# SMC.net
KiCad netlist of a schematic drawn in Altium Designer
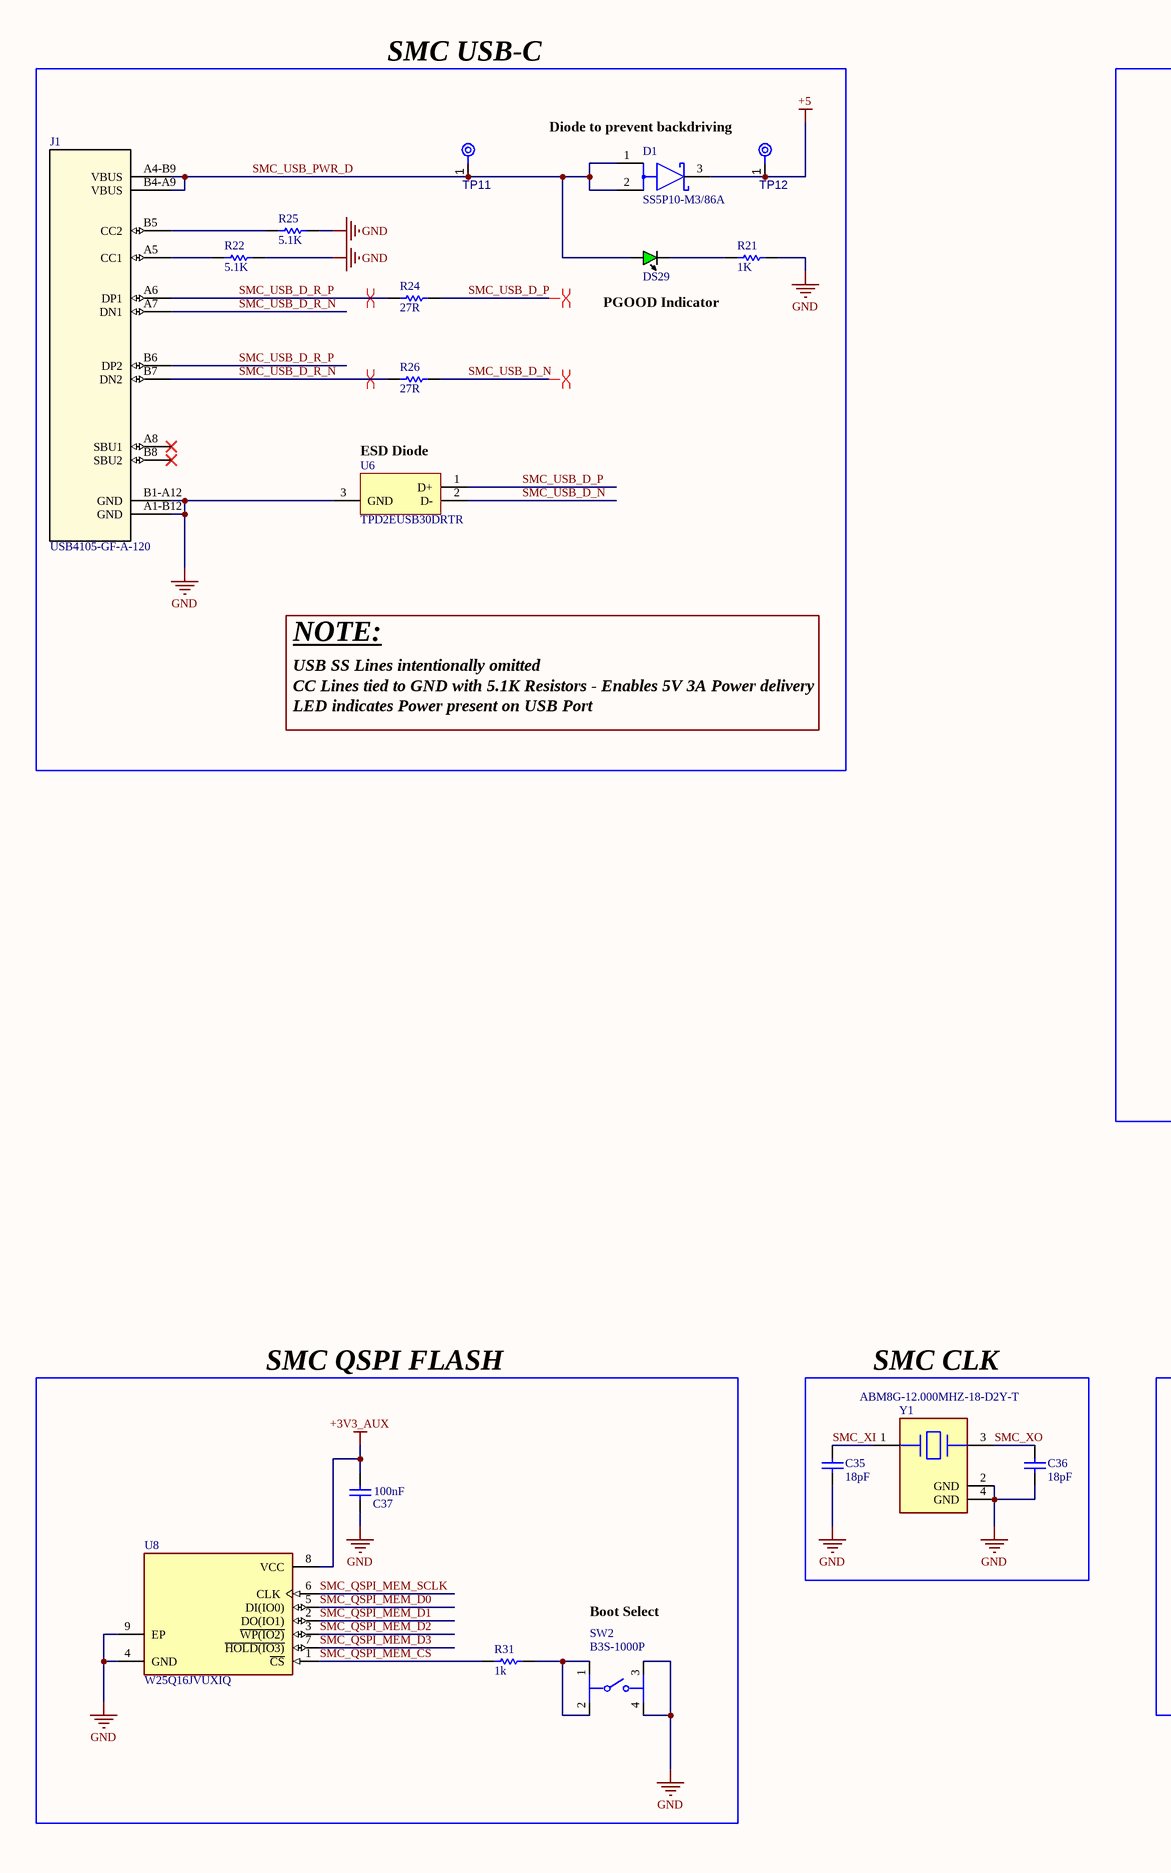
[diagram p0: SMC.SchDoc, left]
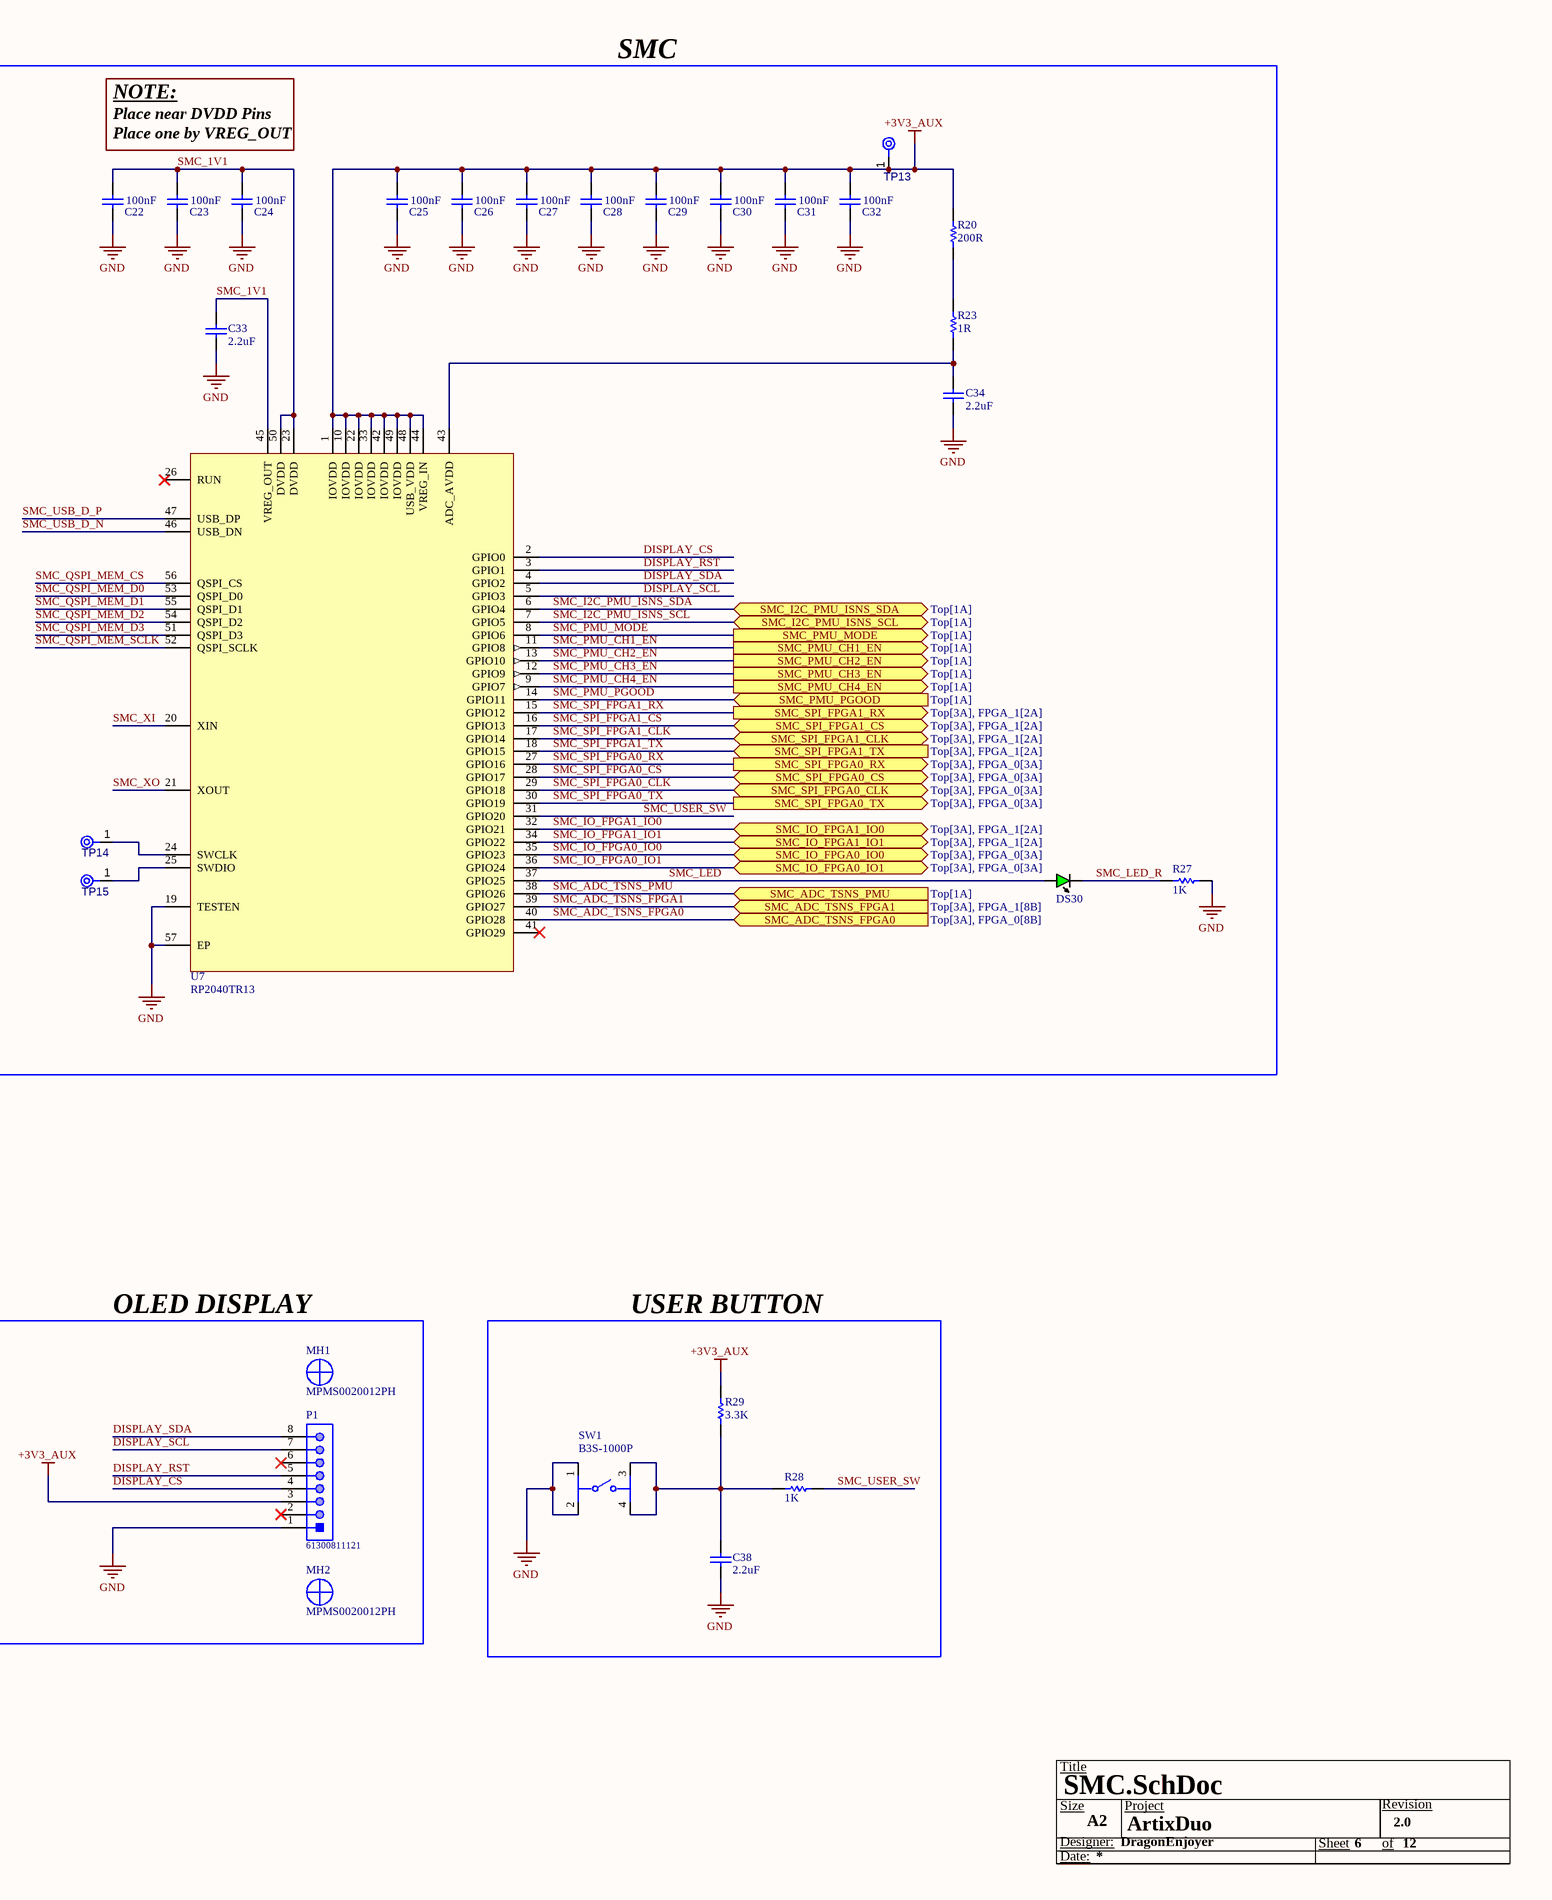
[diagram p1: SMC.SchDoc, right]

(export (version "E")
  (design (tool "Eeschema 10.0.6"))
  (components
    (comp (ref "C22")
      (value "100nF")
      (footprint "CAPC1005X05N")
      (description "Cap Ceramic 0.1uF 50V X7R 20% SMD 0402 125°C Paper T/R GRM155R71H104ME14J")
      (fields (field (name "VOLTAGE") "50V"))
      (libsource (lib "Main Workspace") (part "CAP"))
    )
    (comp (ref "C23")
      (value "100nF")
      (footprint "CAPC1005X05N")
      (description "Cap Ceramic 0.1uF 50V X7R 20% SMD 0402 125°C Paper T/R GRM155R71H104ME14J")
      (fields (field (name "VOLTAGE") "50V"))
      (libsource (lib "Main Workspace") (part "CAP"))
    )
    (comp (ref "C24")
      (value "100nF")
      (footprint "CAPC1005X05N")
      (description "Cap Ceramic 0.1uF 50V X7R 20% SMD 0402 125°C Paper T/R GRM155R71H104ME14J")
      (fields (field (name "VOLTAGE") "50V"))
      (libsource (lib "Main Workspace") (part "CAP"))
    )
    (comp (ref "C25")
      (value "100nF")
      (footprint "CAPC1005X05N")
      (description "Cap Ceramic 0.1uF 50V X7R 20% SMD 0402 125°C Paper T/R GRM155R71H104ME14J")
      (fields (field (name "VOLTAGE") "50V"))
      (libsource (lib "Main Workspace") (part "CAP"))
    )
    (comp (ref "C26")
      (value "100nF")
      (footprint "CAPC1005X05N")
      (description "Cap Ceramic 0.1uF 50V X7R 20% SMD 0402 125°C Paper T/R GRM155R71H104ME14J")
      (fields (field (name "VOLTAGE") "50V"))
      (libsource (lib "Main Workspace") (part "CAP"))
    )
    (comp (ref "C27")
      (value "100nF")
      (footprint "CAPC1005X05N")
      (description "Cap Ceramic 0.1uF 50V X7R 20% SMD 0402 125°C Paper T/R GRM155R71H104ME14J")
      (fields (field (name "VOLTAGE") "50V"))
      (libsource (lib "Main Workspace") (part "CAP"))
    )
    (comp (ref "C28")
      (value "100nF")
      (footprint "CAPC1005X05N")
      (description "Cap Ceramic 0.1uF 50V X7R 20% SMD 0402 125°C Paper T/R GRM155R71H104ME14J")
      (fields (field (name "VOLTAGE") "50V"))
      (libsource (lib "Main Workspace") (part "CAP"))
    )
    (comp (ref "C29")
      (value "100nF")
      (footprint "CAPC1005X05N")
      (description "Cap Ceramic 0.1uF 50V X7R 20% SMD 0402 125°C Paper T/R GRM155R71H104ME14J")
      (fields (field (name "VOLTAGE") "50V"))
      (libsource (lib "Main Workspace") (part "CAP"))
    )
    (comp (ref "C30")
      (value "100nF")
      (footprint "CAPC1005X05N")
      (description "Cap Ceramic 0.1uF 50V X7R 20% SMD 0402 125°C Paper T/R GRM155R71H104ME14J")
      (fields (field (name "VOLTAGE") "50V"))
      (libsource (lib "Main Workspace") (part "CAP"))
    )
    (comp (ref "C31")
      (value "100nF")
      (footprint "CAPC1005X05N")
      (description "Cap Ceramic 0.1uF 50V X7R 20% SMD 0402 125°C Paper T/R GRM155R71H104ME14J")
      (fields (field (name "VOLTAGE") "50V"))
      (libsource (lib "Main Workspace") (part "CAP"))
    )
    (comp (ref "C32")
      (value "100nF")
      (footprint "CAPC1005X05N")
      (description "Cap Ceramic 0.1uF 50V X7R 20% SMD 0402 125°C Paper T/R GRM155R71H104ME14J")
      (fields (field (name "VOLTAGE") "50V"))
      (libsource (lib "Main Workspace") (part "CAP"))
    )
    (comp (ref "C33")
      (value "2.2uF")
      (footprint "CAPC1005X55X25NL05T10")
      (description "GRM155R60J225ME15D")
      (fields (field (name "MANUFACTURER") "Murata"))
      (libsource (lib "Altium Content Vault") (part "CAP"))
    )
    (comp (ref "C34")
      (value "2.2uF")
      (footprint "CAPC1005X55X25NL05T10")
      (description "GRM155R60J225ME15D")
      (fields (field (name "MANUFACTURER") "Murata"))
      (libsource (lib "Altium Content Vault") (part "CAP"))
    )
    (comp (ref "C35")
      (value "18pF")
      (footprint "CAPC1005X55X25LL05T10")
      (fields (field (name "MANUFACTURER") "Murata") (field (name "TOLERANCE") "±5%"))
      (libsource (lib "Altium Content Vault") (part "CAP-NP-2"))
    )
    (comp (ref "C36")
      (value "18pF")
      (footprint "CAPC1005X55X25LL05T10")
      (fields (field (name "MANUFACTURER") "Murata") (field (name "TOLERANCE") "±5%"))
      (libsource (lib "Altium Content Vault") (part "CAP-NP-2"))
    )
    (comp (ref "C37")
      (value "100nF")
      (footprint "CAPC1005X05N")
      (description "Cap Ceramic 0.1uF 50V X7R 20% SMD 0402 125°C Paper T/R GRM155R71H104ME14J")
      (fields (field (name "VOLTAGE") "50V"))
      (libsource (lib "Main Workspace") (part "CAP"))
    )
    (comp (ref "C38")
      (value "2.2uF")
      (footprint "CAPC1005X55X25NL05T10")
      (description "GRM155R60J225ME15D")
      (fields (field (name "MANUFACTURER") "Murata"))
      (libsource (lib "Altium Content Vault") (part "CAP"))
    )
    (comp (ref "D1")
      (value "SS5P10-M3/86A")
      (footprint "FP-95570-MFG")
      (description "DIODE SCHOTTKY 100V 5A TO277A")
      (libsource (lib "Altium Content Vault") (part "03725f8997c85b601c823eea96032f8"))
    )
    (comp (ref "DS29")
      (value "SMLLX0603GWTR")
      (footprint "LUMX-SML-LX0603_V")
      (description "LED GREEN DIFFUSED SMD")
      (libsource (lib "Main Workspace") (part "LED-GREEN-AK-2"))
    )
    (comp (ref "DS30")
      (value "SMLLX0603GWTR")
      (footprint "LUMX-SML-LX0603_V")
      (description "LED GREEN DIFFUSED SMD")
      (libsource (lib "Main Workspace") (part "LED-GREEN-AK-2"))
    )
    (comp (ref "J1")
      (value "USB4105-GF-A-120")
      (footprint "USB4105-GF-A-120-Footprint-1")
      (libsource (lib "Main Workspace") (part "USB4105-GF-A-120"))
    )
    (comp (ref "MH1")
      (value "MPMS0020012PH")
      (footprint "BF-MPMS0020012PH")
      (description "Copper Pillar, M2 Screw")
      (fields (field (name "MANUFACTURER") "B&F Fastener Supply"))
      (libsource (lib "Main Workspace") (part "BF-MPMS0020012PH"))
    )
    (comp (ref "MH2")
      (value "MPMS0020012PH")
      (footprint "BF-MPMS0020012PH")
      (description "Copper Pillar, M2 Screw")
      (fields (field (name "MANUFACTURER") "B&F Fastener Supply"))
      (libsource (lib "Main Workspace") (part "BF-MPMS0020012PH"))
    )
    (comp (ref "P1")
      (value "61300811121")
      (footprint "61300811121")
      (description "THT Vertical Pin Header WR-PHD, Pitch 2.54 mm, Single Row, 8 pins")
      (fields (field (name "MANUFACTURER") "Wurth Elektronik") (field (name "PUBLISHER") "WurthElektronik"))
      (libsource (lib "Altium Content Vault") (part "WE-CN-1P-M-R8"))
    )
    (comp (ref "R20")
      (value "200R")
      (footprint "RESC1005X40X25NL05T05")
      (description "CRCW0402200RJNED")
      (fields (field (name "MANUFACTURER") "Vishay Dale"))
      (libsource (lib "Altium Content Vault") (part "RES"))
    )
    (comp (ref "R21")
      (value "1K")
      (footprint "RESC1005X40X25NL05T10")
      (description "CRCW04021K00FKEDHP")
      (fields (field (name "MANUFACTURER") "Vishay Dale"))
      (libsource (lib "Altium Content Vault") (part "RES"))
    )
    (comp (ref "R22")
      (value "5.1K")
      (footprint "RESC1005X40X25NL05T10")
      (description "RC0402FR-075K1L")
      (fields (field (name "MANUFACTURER") "Yageo / Phycomp"))
      (libsource (lib "Altium Content Vault") (part "RES"))
    )
    (comp (ref "R23")
      (value "1R")
      (footprint "RESC1005X40X25NL05T05")
      (description "CRCW04021R00FKED")
      (fields (field (name "MANUFACTURER") "Vishay Dale"))
      (libsource (lib "Altium Content Vault") (part "RES"))
    )
    (comp (ref "R24")
      (value "27R")
      (footprint "RESC1005X40X25NL05T10")
      (description "RC0402JR-0727RL")
      (fields (field (name "MANUFACTURER") "Yageo / Phycomp"))
      (libsource (lib "Altium Content Vault") (part "RES"))
    )
    (comp (ref "R25")
      (value "5.1K")
      (footprint "RESC1005X40X25NL05T10")
      (description "RC0402FR-075K1L")
      (fields (field (name "MANUFACTURER") "Yageo / Phycomp"))
      (libsource (lib "Altium Content Vault") (part "RES"))
    )
    (comp (ref "R26")
      (value "27R")
      (footprint "RESC1005X40X25NL05T10")
      (description "RC0402JR-0727RL")
      (fields (field (name "MANUFACTURER") "Yageo / Phycomp"))
      (libsource (lib "Altium Content Vault") (part "RES"))
    )
    (comp (ref "R27")
      (value "1K")
      (footprint "RESC1005X40X25NL05T10")
      (description "CRCW04021K00FKEDHP")
      (fields (field (name "MANUFACTURER") "Vishay Dale"))
      (libsource (lib "Altium Content Vault") (part "RES"))
    )
    (comp (ref "R28")
      (value "1K")
      (footprint "RESC1005X40X25NL05T10")
      (description "CRCW04021K00FKEDHP")
      (fields (field (name "MANUFACTURER") "Vishay Dale"))
      (libsource (lib "Altium Content Vault") (part "RES"))
    )
    (comp (ref "R29")
      (value "3.3K")
      (footprint "RESC1005X40X25NL05T10")
      (description "CRCW04023K30FKEDHP")
      (fields (field (name "MANUFACTURER") "Vishay Dale"))
      (libsource (lib "Altium Content Vault") (part "RES"))
    )
    (comp (ref "R31")
      (value "1k")
      (footprint "RESC1005X40X25ML05T05")
      (description "Chip Resistor, 1 KOhm, +/- 1%, 0.1 W, -55 to 155 degC, 0402 (1005 Metric)")
      (fields (field (name "POWER") "100mW") (field (name "TOLERANCE") "1%"))
      (libsource (lib "Main Workspace") (part "RES-2"))
    )
    (comp (ref "SW1")
      (value "B3S-1000P")
      (footprint "FP-B3S-1000P-MFG")
      (description "SWITCH TACTILE SPST-NO 0.05A 24V")
      (libsource (lib "Altium Content Vault") (part "b8895f3f4cefb76e1819d2863dba89b"))
    )
    (comp (ref "SW2")
      (value "B3S-1000P")
      (footprint "FP-B3S-1000P-MFG")
      (description "SWITCH TACTILE SPST-NO 0.05A 24V")
      (libsource (lib "Altium Content Vault") (part "b8895f3f4cefb76e1819d2863dba89b"))
    )
    (comp (ref "TP11")
      (value "TPAD6R")
      (footprint "TP06R")
      (description "0.6mm round")
      (libsource (lib "Main Workspace") (part "CMP-001-0001-4"))
    )
    (comp (ref "TP12")
      (value "TPAD6R")
      (footprint "TP06R")
      (description "0.6mm round")
      (libsource (lib "Main Workspace") (part "CMP-001-0001-4"))
    )
    (comp (ref "TP13")
      (value "TPAD6R")
      (footprint "TP06R")
      (description "0.6mm round")
      (libsource (lib "Main Workspace") (part "CMP-001-0001-4"))
    )
    (comp (ref "TP14")
      (value "TPAD6R")
      (footprint "TP06R")
      (description "0.6mm round")
      (libsource (lib "Main Workspace") (part "CMP-001-0001-4"))
    )
    (comp (ref "TP15")
      (value "TPAD6R")
      (footprint "TP06R")
      (description "0.6mm round")
      (libsource (lib "Main Workspace") (part "CMP-001-0001-4"))
    )
    (comp (ref "U6")
      (value "TPD2EUSB30DRTR")
      (footprint "DRT0003A")
      (fields (field (name "MANUFACTURER") "Texas Instruments"))
      (libsource (lib "Altium Content Vault") (part "TI-TPD2EUSB30-SOT_DRT-3"))
    )
    (comp (ref "U7")
      (value "RP2040TR13")
      (footprint "QFN40P700X700X80_HS-57N")
      (description "Mcu, 32 Bit, 133MHZ, QFN-56;")
      (libsource (lib "Main Workspace") (part "RP2040"))
    )
    (comp (ref "U8")
      (value "W25Q16JVUXIQ")
      (footprint "FP-UX-MFG")
      (description "IC FLASH 16MBIT SPI/QUAD 8USON")
      (libsource (lib "Altium Content Vault") (part "ef7e6bbff5b18f94b0c5acc221a373e"))
    )
    (comp (ref "Y1")
      (value "ABM8G-12.000MHZ-18-D2Y-T")
      (footprint "FP-ABM8G-MFG")
      (description "Crystal 12MHz ±20ppm (Tol) ±30ppm (Stability) 18pF FUND 120Ω 4-Pin SMD T/R")
      (fields (field (name "TOLERANCE") "20ppm"))
      (libsource (lib "Altium Content Vault") (part "48e526d86b7f2615d98721063c72f49"))
    )
  )
  (nets
    (net (code "1") (name "+3V3_AUX") (class "Default")
      (node (ref "C25") (pin "2") (pinfunction "2_2") (pintype "passive"))
      (node (ref "C26") (pin "2") (pinfunction "2_2") (pintype "passive"))
      (node (ref "C27") (pin "2") (pinfunction "2_2") (pintype "passive"))
      (node (ref "C28") (pin "2") (pinfunction "2_2") (pintype "passive"))
      (node (ref "C29") (pin "2") (pinfunction "2_2") (pintype "passive"))
      (node (ref "C30") (pin "2") (pinfunction "2_2") (pintype "passive"))
      (node (ref "C31") (pin "2") (pinfunction "2_2") (pintype "passive"))
      (node (ref "C32") (pin "2") (pinfunction "2_2") (pintype "passive"))
      (node (ref "C37") (pin "2") (pinfunction "2_2") (pintype "passive"))
      (node (ref "P1") (pin "3") (pinfunction "3_3") (pintype "passive"))
      (node (ref "R20") (pin "2") (pinfunction "2_2") (pintype "passive"))
      (node (ref "R29") (pin "2") (pinfunction "2_2") (pintype "passive"))
      (node (ref "TP13") (pin "1") (pinfunction "TP_1") (pintype "passive"))
      (node (ref "U7") (pin "1") (pinfunction "IOVDD_1") (pintype "passive"))
      (node (ref "U7") (pin "10") (pinfunction "IOVDD_10") (pintype "passive"))
      (node (ref "U7") (pin "22") (pinfunction "IOVDD_22") (pintype "passive"))
      (node (ref "U7") (pin "33") (pinfunction "IOVDD_33") (pintype "passive"))
      (node (ref "U7") (pin "42") (pinfunction "IOVDD_42") (pintype "passive"))
      (node (ref "U7") (pin "44") (pinfunction "VREG_IN_44") (pintype "passive"))
      (node (ref "U7") (pin "48") (pinfunction "USB_VDD_48") (pintype "passive"))
      (node (ref "U7") (pin "49") (pinfunction "IOVDD_49") (pintype "passive"))
      (node (ref "U8") (pin "8") (pinfunction "VCC_8") (pintype "power_in"))
    )
    (net (code "2") (name "+5") (class "Default")
      (node (ref "D1") (pin "3") (pinfunction "C_3") (pintype "passive"))
      (node (ref "TP12") (pin "1") (pinfunction "TP_1") (pintype "passive"))
    )
    (net (code "4") (name "/DISPLAY_CS") (class "Default")
      (node (ref "P1") (pin "4") (pinfunction "4_4") (pintype "passive"))
      (node (ref "U7") (pin "2") (pinfunction "GPIO0_2") (pintype "passive"))
    )
    (net (code "5") (name "/DISPLAY_RST") (class "Default")
      (node (ref "P1") (pin "5") (pinfunction "5_5") (pintype "passive"))
      (node (ref "U7") (pin "3") (pinfunction "GPIO1_3") (pintype "passive"))
    )
    (net (code "6") (name "/DISPLAY_SCL") (class "Default")
      (node (ref "P1") (pin "7") (pinfunction "7_7") (pintype "passive"))
      (node (ref "U7") (pin "5") (pinfunction "GPIO3_5") (pintype "passive"))
    )
    (net (code "7") (name "/DISPLAY_SDA") (class "Default")
      (node (ref "P1") (pin "8") (pinfunction "8_8") (pintype "passive"))
      (node (ref "U7") (pin "4") (pinfunction "GPIO2_4") (pintype "passive"))
    )
    (net (code "8") (name "/SMC_1V1") (class "Default")
      (node (ref "C22") (pin "2") (pinfunction "2_2") (pintype "passive"))
      (node (ref "C23") (pin "2") (pinfunction "2_2") (pintype "passive"))
      (node (ref "C24") (pin "2") (pinfunction "2_2") (pintype "passive"))
      (node (ref "C33") (pin "2") (pinfunction "2_2") (pintype "passive"))
      (node (ref "U7") (pin "23") (pinfunction "DVDD_23") (pintype "passive"))
      (node (ref "U7") (pin "45") (pinfunction "VREG_OUT_45") (pintype "passive"))
      (node (ref "U7") (pin "50") (pinfunction "DVDD_50") (pintype "passive"))
    )
    (net (code "9") (name "/SMC_ADC_TSNS_FPGA0") (class "Default")
      (node (ref "U7") (pin "40") (pinfunction "GPIO28_40") (pintype "passive"))
    )
    (net (code "10") (name "/SMC_ADC_TSNS_FPGA1") (class "Default")
      (node (ref "U7") (pin "39") (pinfunction "GPIO27_39") (pintype "passive"))
    )
    (net (code "11") (name "/SMC_ADC_TSNS_PMU") (class "Default")
      (node (ref "U7") (pin "38") (pinfunction "GPIO26_38") (pintype "passive"))
    )
    (net (code "12") (name "/SMC_I2C_PMU_ISNS_SCL") (class "Default")
      (node (ref "U7") (pin "7") (pinfunction "GPIO5_7") (pintype "passive"))
    )
    (net (code "13") (name "/SMC_I2C_PMU_ISNS_SDA") (class "Default")
      (node (ref "U7") (pin "6") (pinfunction "GPIO4_6") (pintype "passive"))
    )
    (net (code "14") (name "/SMC_IO_FPGA0_IO0") (class "Default")
      (node (ref "U7") (pin "35") (pinfunction "GPIO23_35") (pintype "passive"))
    )
    (net (code "15") (name "/SMC_IO_FPGA0_IO1") (class "Default")
      (node (ref "U7") (pin "36") (pinfunction "GPIO24_36") (pintype "passive"))
    )
    (net (code "16") (name "/SMC_IO_FPGA1_IO0") (class "Default")
      (node (ref "U7") (pin "32") (pinfunction "GPIO21_32") (pintype "passive"))
    )
    (net (code "17") (name "/SMC_IO_FPGA1_IO1") (class "Default")
      (node (ref "U7") (pin "34") (pinfunction "GPIO22_34") (pintype "passive"))
    )
    (net (code "18") (name "/SMC_LED") (class "Default")
      (node (ref "DS30") (pin "1") (pinfunction "A_1") (pintype "passive"))
      (node (ref "U7") (pin "37") (pinfunction "GPIO25_37") (pintype "passive"))
    )
    (net (code "19") (name "/SMC_LED_R") (class "Default")
      (node (ref "DS30") (pin "2") (pinfunction "K_2") (pintype "passive"))
      (node (ref "R27") (pin "2") (pinfunction "2_2") (pintype "passive"))
    )
    (net (code "20") (name "/SMC_PMU_CH1_EN") (class "Default")
      (node (ref "U7") (pin "11") (pinfunction "GPIO8_11") (pintype "output"))
    )
    (net (code "21") (name "/SMC_PMU_CH2_EN") (class "Default")
      (node (ref "U7") (pin "13") (pinfunction "GPIO10_13") (pintype "output"))
    )
    (net (code "22") (name "/SMC_PMU_CH3_EN") (class "Default")
      (node (ref "U7") (pin "12") (pinfunction "GPIO9_12") (pintype "output"))
    )
    (net (code "23") (name "/SMC_PMU_CH4_EN") (class "Default")
      (node (ref "U7") (pin "9") (pinfunction "GPIO7_9") (pintype "output"))
    )
    (net (code "24") (name "/SMC_PMU_MODE") (class "Default")
      (node (ref "U7") (pin "8") (pinfunction "GPIO6_8") (pintype "passive"))
    )
    (net (code "25") (name "/SMC_PMU_PGOOD") (class "Default")
      (node (ref "U7") (pin "14") (pinfunction "GPIO11_14") (pintype "passive"))
    )
    (net (code "26") (name "/SMC_QSPI_MEM_CS") (class "Default")
      (node (ref "R31") (pin "1") (pinfunction "1_1") (pintype "passive"))
      (node (ref "U7") (pin "56") (pinfunction "QSPI_CS_56") (pintype "passive"))
      (node (ref "U8") (pin "1") (pinfunction "~{CS}_1") (pintype "input"))
    )
    (net (code "27") (name "/SMC_QSPI_MEM_D0") (class "Default")
      (node (ref "U7") (pin "53") (pinfunction "QSPI_D0_53") (pintype "passive"))
      (node (ref "U8") (pin "5") (pinfunction "DI(IO0)_5") (pintype "bidirectional"))
    )
    (net (code "28") (name "/SMC_QSPI_MEM_D1") (class "Default")
      (node (ref "U7") (pin "55") (pinfunction "QSPI_D1_55") (pintype "passive"))
      (node (ref "U8") (pin "2") (pinfunction "DO(IO1)_2") (pintype "bidirectional"))
    )
    (net (code "29") (name "/SMC_QSPI_MEM_D2") (class "Default")
      (node (ref "U7") (pin "54") (pinfunction "QSPI_D2_54") (pintype "passive"))
      (node (ref "U8") (pin "3") (pinfunction "~{WP(IO2)}_3") (pintype "bidirectional"))
    )
    (net (code "30") (name "/SMC_QSPI_MEM_D3") (class "Default")
      (node (ref "U7") (pin "51") (pinfunction "QSPI_D3_51") (pintype "passive"))
      (node (ref "U8") (pin "7") (pinfunction "~{HOLD(IO3)}_7") (pintype "bidirectional"))
    )
    (net (code "31") (name "/SMC_QSPI_MEM_SCLK") (class "Default")
      (node (ref "U7") (pin "52") (pinfunction "QSPI_SCLK_52") (pintype "passive"))
      (node (ref "U8") (pin "6") (pinfunction "CLK_6") (pintype "input"))
    )
    (net (code "32") (name "/SMC_SPI_FPGA0_CLK") (class "Default")
      (node (ref "U7") (pin "29") (pinfunction "GPIO18_29") (pintype "passive"))
    )
    (net (code "33") (name "/SMC_SPI_FPGA0_CS") (class "Default")
      (node (ref "U7") (pin "28") (pinfunction "GPIO17_28") (pintype "passive"))
    )
    (net (code "34") (name "/SMC_SPI_FPGA0_RX") (class "Default")
      (node (ref "U7") (pin "27") (pinfunction "GPIO16_27") (pintype "passive"))
    )
    (net (code "35") (name "/SMC_SPI_FPGA0_TX") (class "Default")
      (node (ref "U7") (pin "30") (pinfunction "GPIO19_30") (pintype "passive"))
    )
    (net (code "36") (name "/SMC_SPI_FPGA1_CLK") (class "Default")
      (node (ref "U7") (pin "17") (pinfunction "GPIO14_17") (pintype "passive"))
    )
    (net (code "37") (name "/SMC_SPI_FPGA1_CS") (class "Default")
      (node (ref "U7") (pin "16") (pinfunction "GPIO13_16") (pintype "passive"))
    )
    (net (code "38") (name "/SMC_SPI_FPGA1_RX") (class "Default")
      (node (ref "U7") (pin "15") (pinfunction "GPIO12_15") (pintype "passive"))
    )
    (net (code "39") (name "/SMC_SPI_FPGA1_TX") (class "Default")
      (node (ref "U7") (pin "18") (pinfunction "GPIO15_18") (pintype "passive"))
    )
    (net (code "40") (name "/SMC_USB_D_N") (class "Default")
      (node (ref "R26") (pin "2") (pinfunction "2_2") (pintype "passive"))
      (node (ref "U6") (pin "2") (pinfunction "D-_2") (pintype "passive"))
      (node (ref "U7") (pin "46") (pinfunction "USB_DN_46") (pintype "passive"))
    )
    (net (code "41") (name "/SMC_USB_D_P") (class "Default")
      (node (ref "R24") (pin "2") (pinfunction "2_2") (pintype "passive"))
      (node (ref "U6") (pin "1") (pinfunction "D+_1") (pintype "passive"))
      (node (ref "U7") (pin "47") (pinfunction "USB_DP_47") (pintype "passive"))
    )
    (net (code "42") (name "/SMC_USB_D_R_N") (class "Default")
      (node (ref "J1") (pin "A7") (pinfunction "DN1_A7") (pintype "bidirectional"))
      (node (ref "J1") (pin "B7") (pinfunction "DN2_B7") (pintype "bidirectional"))
      (node (ref "R26") (pin "1") (pinfunction "1_1") (pintype "passive"))
    )
    (net (code "43") (name "/SMC_USB_D_R_P") (class "Default")
      (node (ref "J1") (pin "A6") (pinfunction "DP1_A6") (pintype "bidirectional"))
      (node (ref "J1") (pin "B6") (pinfunction "DP2_B6") (pintype "bidirectional"))
      (node (ref "R24") (pin "1") (pinfunction "1_1") (pintype "passive"))
    )
    (net (code "44") (name "/SMC_USB_PWR_D") (class "Default")
      (node (ref "D1") (pin "1") (pinfunction "A_1") (pintype "passive"))
      (node (ref "D1") (pin "2") (pinfunction "A_2") (pintype "passive"))
      (node (ref "DS29") (pin "1") (pinfunction "A_1") (pintype "passive"))
      (node (ref "J1") (pin "A4-B9") (pinfunction "VBUS_A4-B9") (pintype "power_in"))
      (node (ref "J1") (pin "B4-A9") (pinfunction "VBUS_B4-A9") (pintype "power_in"))
      (node (ref "TP11") (pin "1") (pinfunction "TP_1") (pintype "passive"))
    )
    (net (code "45") (name "/SMC_USER_SW") (class "Default")
      (node (ref "R28") (pin "1") (pinfunction "1_1") (pintype "passive"))
      (node (ref "U7") (pin "31") (pinfunction "GPIO20_31") (pintype "passive"))
    )
    (net (code "46") (name "/SMC_XI") (class "Default")
      (node (ref "C35") (pin "2") (pinfunction "2_2") (pintype "passive"))
      (node (ref "U7") (pin "20") (pinfunction "XIN_20") (pintype "passive"))
      (node (ref "Y1") (pin "1") (pinfunction "1_1") (pintype "passive"))
    )
    (net (code "47") (name "/SMC_XO") (class "Default")
      (node (ref "C36") (pin "2") (pinfunction "2_2") (pintype "passive"))
      (node (ref "U7") (pin "21") (pinfunction "XOUT_21") (pintype "passive"))
      (node (ref "Y1") (pin "3") (pinfunction "3_3") (pintype "passive"))
    )
    (net (code "48") (name "GND") (class "Default")
      (node (ref "C22") (pin "1") (pinfunction "1_1") (pintype "passive"))
      (node (ref "C23") (pin "1") (pinfunction "1_1") (pintype "passive"))
      (node (ref "C24") (pin "1") (pinfunction "1_1") (pintype "passive"))
      (node (ref "C25") (pin "1") (pinfunction "1_1") (pintype "passive"))
      (node (ref "C26") (pin "1") (pinfunction "1_1") (pintype "passive"))
      (node (ref "C27") (pin "1") (pinfunction "1_1") (pintype "passive"))
      (node (ref "C28") (pin "1") (pinfunction "1_1") (pintype "passive"))
      (node (ref "C29") (pin "1") (pinfunction "1_1") (pintype "passive"))
      (node (ref "C30") (pin "1") (pinfunction "1_1") (pintype "passive"))
      (node (ref "C31") (pin "1") (pinfunction "1_1") (pintype "passive"))
      (node (ref "C32") (pin "1") (pinfunction "1_1") (pintype "passive"))
      (node (ref "C33") (pin "1") (pinfunction "1_1") (pintype "passive"))
      (node (ref "C34") (pin "1") (pinfunction "1_1") (pintype "passive"))
      (node (ref "C35") (pin "1") (pinfunction "1_1") (pintype "passive"))
      (node (ref "C36") (pin "1") (pinfunction "1_1") (pintype "passive"))
      (node (ref "C37") (pin "1") (pinfunction "1_1") (pintype "passive"))
      (node (ref "C38") (pin "1") (pinfunction "1_1") (pintype "passive"))
      (node (ref "J1") (pin "A1-B12") (pinfunction "GND_A1-B12") (pintype "power_in"))
      (node (ref "J1") (pin "B1-A12") (pinfunction "GND_B1-A12") (pintype "power_in"))
      (node (ref "P1") (pin "1") (pinfunction "1_1") (pintype "passive"))
      (node (ref "R21") (pin "1") (pinfunction "1_1") (pintype "passive"))
      (node (ref "R22") (pin "2") (pinfunction "2_2") (pintype "passive"))
      (node (ref "R25") (pin "2") (pinfunction "2_2") (pintype "passive"))
      (node (ref "R27") (pin "1") (pinfunction "1_1") (pintype "passive"))
      (node (ref "SW1") (pin "1") (pinfunction "1_1") (pintype "passive"))
      (node (ref "SW1") (pin "2") (pinfunction "2_2") (pintype "passive"))
      (node (ref "SW2") (pin "3") (pinfunction "3_3") (pintype "passive"))
      (node (ref "SW2") (pin "4") (pinfunction "4_4") (pintype "passive"))
      (node (ref "U6") (pin "3") (pinfunction "GND_3") (pintype "power_in"))
      (node (ref "U7") (pin "19") (pinfunction "TESTEN_19") (pintype "passive"))
      (node (ref "U7") (pin "57") (pinfunction "EP_57") (pintype "passive"))
      (node (ref "U8") (pin "4") (pinfunction "GND_4") (pintype "power_in"))
      (node (ref "U8") (pin "9") (pinfunction "EP_9") (pintype "passive"))
      (node (ref "Y1") (pin "2") (pinfunction "GND_2") (pintype "power_in"))
      (node (ref "Y1") (pin "4") (pinfunction "GND_4") (pintype "power_in"))
    )
    (net (code "49") (name "Net-(C38-Pad2)") (class "Default")
      (node (ref "C38") (pin "2") (pinfunction "2_2") (pintype "passive"))
      (node (ref "R28") (pin "2") (pinfunction "2_2") (pintype "passive"))
      (node (ref "R29") (pin "1") (pinfunction "1_1") (pintype "passive"))
      (node (ref "SW1") (pin "3") (pinfunction "3_3") (pintype "passive"))
      (node (ref "SW1") (pin "4") (pinfunction "4_4") (pintype "passive"))
    )
    (net (code "50") (name "Net-(DS29-K)") (class "Default")
      (node (ref "DS29") (pin "2") (pinfunction "K_2") (pintype "passive"))
      (node (ref "R21") (pin "2") (pinfunction "2_2") (pintype "passive"))
    )
    (net (code "51") (name "Net-(J1-CC1)") (class "Default")
      (node (ref "J1") (pin "A5") (pinfunction "CC1_A5") (pintype "bidirectional"))
      (node (ref "R22") (pin "1") (pinfunction "1_1") (pintype "passive"))
    )
    (net (code "52") (name "Net-(J1-CC2)") (class "Default")
      (node (ref "J1") (pin "B5") (pinfunction "CC2_B5") (pintype "bidirectional"))
      (node (ref "R25") (pin "1") (pinfunction "1_1") (pintype "passive"))
    )
    (net (code "53") (name "Net-(R20-Pad1)") (class "Default")
      (node (ref "R20") (pin "1") (pinfunction "1_1") (pintype "passive"))
      (node (ref "R23") (pin "2") (pinfunction "2_2") (pintype "passive"))
    )
    (net (code "54") (name "Net-(R31-Pad2)") (class "Default")
      (node (ref "R31") (pin "2") (pinfunction "2_2") (pintype "passive"))
      (node (ref "SW2") (pin "1") (pinfunction "1_1") (pintype "passive"))
      (node (ref "SW2") (pin "2") (pinfunction "2_2") (pintype "passive"))
    )
    (net (code "55") (name "Net-(TP14-TP)") (class "Default")
      (node (ref "TP14") (pin "1") (pinfunction "TP_1") (pintype "passive"))
      (node (ref "U7") (pin "24") (pinfunction "SWCLK_24") (pintype "passive"))
    )
    (net (code "56") (name "Net-(TP15-TP)") (class "Default")
      (node (ref "TP15") (pin "1") (pinfunction "TP_1") (pintype "passive"))
      (node (ref "U7") (pin "25") (pinfunction "SWDIO_25") (pintype "passive"))
    )
    (net (code "57") (name "Net-(U7-ADC_AVDD)") (class "Default")
      (node (ref "C34") (pin "2") (pinfunction "2_2") (pintype "passive"))
      (node (ref "R23") (pin "1") (pinfunction "1_1") (pintype "passive"))
      (node (ref "U7") (pin "43") (pinfunction "ADC_AVDD_43") (pintype "passive"))
    )
    (net (code "58") (name "unconnected-(J1-SBU1-PadA8)") (class "Default")
      (node (ref "J1") (pin "A8") (pinfunction "SBU1_A8") (pintype "bidirectional+no_connect"))
    )
    (net (code "59") (name "unconnected-(J1-SBU2-PadB8)") (class "Default")
      (node (ref "J1") (pin "B8") (pinfunction "SBU2_B8") (pintype "bidirectional+no_connect"))
    )
    (net (code "60") (name "unconnected-(MH1-Pad1)") (class "Default")
      (node (ref "MH1") (pin "1") (pinfunction "1_1") (pintype "passive"))
    )
    (net (code "61") (name "unconnected-(MH2-Pad1)") (class "Default")
      (node (ref "MH2") (pin "1") (pinfunction "1_1") (pintype "passive"))
    )
    (net (code "62") (name "unconnected-(P1-Pad2)") (class "Default")
      (node (ref "P1") (pin "2") (pinfunction "2_2") (pintype "passive+no_connect"))
    )
    (net (code "63") (name "unconnected-(P1-Pad6)") (class "Default")
      (node (ref "P1") (pin "6") (pinfunction "6_6") (pintype "passive+no_connect"))
    )
    (net (code "64") (name "unconnected-(U7-GPIO29-Pad41)") (class "Default")
      (node (ref "U7") (pin "41") (pinfunction "GPIO29_41") (pintype "passive+no_connect"))
    )
    (net (code "65") (name "unconnected-(U7-RUN-Pad26)") (class "Default")
      (node (ref "U7") (pin "26") (pinfunction "RUN_26") (pintype "passive+no_connect"))
    )
  )
)
